# Schematic.net
KiCad netlist of a schematic drawn in EAGLE
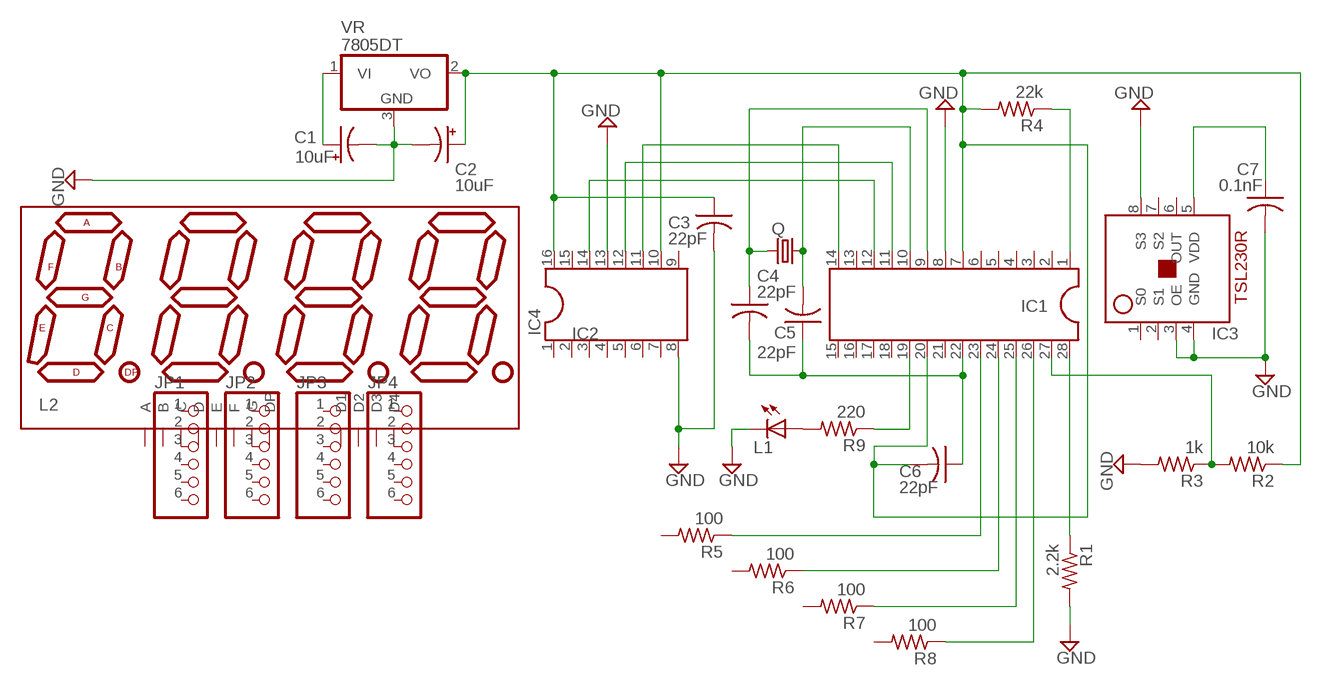
[diagram p0: schematic, sheet 1]

(export (version "E")
  (design (tool "Eeschema 10.0.6"))
  (components
    (comp (ref "C1")
      (value "10uF")
      (footprint "eagle-import:140CLH-1010")
      (libsource (lib "eagle-import") (part "CPOL-US140CLH-1010"))
    )
    (comp (ref "C2")
      (value "10uF")
      (footprint "eagle-import:140CLH-1010")
      (libsource (lib "eagle-import") (part "CPOL-US140CLH-1010"))
    )
    (comp (ref "C3")
      (value "22pF")
      (footprint "eagle-import:C025-024X044")
      (libsource (lib "eagle-import") (part "C-US025-024X044"))
    )
    (comp (ref "C4")
      (value "22pF")
      (footprint "eagle-import:C025-024X044")
      (libsource (lib "eagle-import") (part "C-US025-024X044"))
    )
    (comp (ref "C5")
      (value "22pF")
      (footprint "eagle-import:C025-024X044")
      (libsource (lib "eagle-import") (part "C-US025-024X044"))
    )
    (comp (ref "C6")
      (value "22pF")
      (footprint "eagle-import:C025-024X044")
      (libsource (lib "eagle-import") (part "C-US025-024X044"))
    )
    (comp (ref "C7")
      (value "0.1nF")
      (footprint "eagle-import:C025-024X044")
      (libsource (lib "eagle-import") (part "C-US025-024X044"))
    )
    (comp (ref "IC1")
      (value "DIL28")
      (footprint "eagle-import:DIL28-6")
      (libsource (lib "eagle-import") (part "DIL28"))
    )
    (comp (ref "IC3")
      (value "LIGHT_TO_FREQ_CONVERTER")
      (footprint "eagle-import:LIGHT_TO_FREQ_CONVERTER")
      (libsource (lib "eagle-import") (part "LIGHT_TO_FREQ_CONVERTER"))
    )
    (comp (ref "IC4")
      (value "DIL16")
      (footprint "eagle-import:DIL16")
      (libsource (lib "eagle-import") (part "DIL16"))
    )
    (comp (ref "JP1")
      (value "PINHD-1X6CLEAN")
      (footprint "eagle-import:1X06-CLEAN")
      (libsource (lib "eagle-import") (part "PINHD-1X6CLEAN"))
    )
    (comp (ref "JP2")
      (value "PINHD-1X6CLEAN")
      (footprint "eagle-import:1X06-CLEAN")
      (libsource (lib "eagle-import") (part "PINHD-1X6CLEAN"))
    )
    (comp (ref "JP3")
      (value "PINHD-1X6CLEAN")
      (footprint "eagle-import:1X06-CLEAN")
      (libsource (lib "eagle-import") (part "PINHD-1X6CLEAN"))
    )
    (comp (ref "JP4")
      (value "PINHD-1X6CLEAN")
      (footprint "eagle-import:1X06-CLEAN")
      (libsource (lib "eagle-import") (part "PINHD-1X6CLEAN"))
    )
    (comp (ref "L1")
      (value "LEDIRL80A")
      (footprint "eagle-import:IRL80A")
      (libsource (lib "eagle-import") (part "LEDIRL80A"))
    )
    (comp (ref "Q")
      (value "CRYSTALHC49S")
      (footprint "eagle-import:HC49_S")
      (libsource (lib "eagle-import") (part "CRYSTALHC49S"))
    )
    (comp (ref "R1")
      (value "2.2k")
      (footprint "eagle-import:0207_12")
      (libsource (lib "eagle-import") (part "R-US_0207/12"))
    )
    (comp (ref "R2")
      (value "10k")
      (footprint "eagle-import:0207_12")
      (libsource (lib "eagle-import") (part "R-US_0207/12"))
    )
    (comp (ref "R3")
      (value "1k")
      (footprint "eagle-import:0207_12")
      (libsource (lib "eagle-import") (part "R-US_0207/12"))
    )
    (comp (ref "R4")
      (value "22k")
      (footprint "eagle-import:0207_12")
      (libsource (lib "eagle-import") (part "R-US_0207/12"))
    )
    (comp (ref "R5")
      (value "100")
      (footprint "eagle-import:0207_12")
      (libsource (lib "eagle-import") (part "R-US_0207/12"))
    )
    (comp (ref "R6")
      (value "100")
      (footprint "eagle-import:0207_12")
      (libsource (lib "eagle-import") (part "R-US_0207/12"))
    )
    (comp (ref "R7")
      (value "100")
      (footprint "eagle-import:0207_12")
      (libsource (lib "eagle-import") (part "R-US_0207/12"))
    )
    (comp (ref "R8")
      (value "100")
      (footprint "eagle-import:0207_12")
      (libsource (lib "eagle-import") (part "R-US_0207/12"))
    )
    (comp (ref "R9")
      (value "220")
      (footprint "eagle-import:0207_12")
      (libsource (lib "eagle-import") (part "R-US_0207/12"))
    )
    (comp (ref "U$1")
      (value "7-SEGMENT-4DIGIT-COUNTERPTH")
      (footprint "eagle-import:7-SEGMENT-4DIGIT-COUNTER")
      (libsource (lib "eagle-import") (part "7-SEGMENT-4DIGIT-COUNTERPTH"))
    )
    (comp (ref "VR")
      (value "7805DT")
      (footprint "eagle-import:TO252")
      (libsource (lib "eagle-import") (part "78DT05"))
    )
  )
  (nets
    (net (code "1") (name "GND") (class "Default")
      (node (ref "C1") (pin "-") (pinfunction "-_-") (pintype "passive"))
      (node (ref "C2") (pin "-") (pinfunction "-_-") (pintype "passive"))
      (node (ref "C3") (pin "2") (pinfunction "2_2") (pintype "passive"))
      (node (ref "C7") (pin "2") (pinfunction "2_2") (pintype "passive"))
      (node (ref "IC1") (pin "8") (pinfunction "8_8") (pintype "passive"))
      (node (ref "IC3") (pin "3") (pinfunction "OE_3") (pintype "bidirectional"))
      (node (ref "IC3") (pin "4") (pinfunction "GND_4") (pintype "bidirectional"))
      (node (ref "IC3") (pin "8") (pinfunction "S3_8") (pintype "bidirectional"))
      (node (ref "IC4") (pin "13") (pinfunction "13_13") (pintype "passive"))
      (node (ref "IC4") (pin "8") (pinfunction "8_8") (pintype "passive"))
      (node (ref "L1") (pin "K") (pinfunction "C_K") (pintype "passive"))
      (node (ref "R1") (pin "2") (pinfunction "2_2") (pintype "passive"))
      (node (ref "R3") (pin "2") (pinfunction "2_2") (pintype "passive"))
      (node (ref "VR") (pin "3") (pinfunction "GND_3") (pintype "passive"))
    )
    (net (code "2") (name "Net-(C4-Pad1)") (class "Default")
      (node (ref "C4") (pin "1") (pinfunction "1_1") (pintype "passive"))
      (node (ref "IC1") (pin "9") (pinfunction "9_9") (pintype "passive"))
      (node (ref "Q") (pin "2") (pinfunction "2_2") (pintype "passive"))
    )
    (net (code "3") (name "Net-(C4-Pad2)") (class "Default")
      (node (ref "C4") (pin "2") (pinfunction "2_2") (pintype "passive"))
      (node (ref "C5") (pin "1") (pinfunction "1_1") (pintype "passive"))
      (node (ref "C6") (pin "1") (pinfunction "1_1") (pintype "passive"))
      (node (ref "IC1") (pin "22") (pinfunction "22_22") (pintype "passive"))
    )
    (net (code "4") (name "Net-(C5-Pad2)") (class "Default")
      (node (ref "C5") (pin "2") (pinfunction "2_2") (pintype "passive"))
      (node (ref "IC1") (pin "10") (pinfunction "10_10") (pintype "passive"))
      (node (ref "Q") (pin "1") (pinfunction "1_1") (pintype "passive"))
    )
    (net (code "5") (name "Net-(IC1-Pad1)") (class "Default")
      (node (ref "IC1") (pin "1") (pinfunction "1_1") (pintype "passive"))
      (node (ref "R4") (pin "1") (pinfunction "1_1") (pintype "passive"))
    )
    (net (code "6") (name "Net-(IC1-Pad11)") (class "Default")
      (node (ref "IC1") (pin "11") (pinfunction "11_11") (pintype "passive"))
      (node (ref "IC4") (pin "12") (pinfunction "12_12") (pintype "passive"))
    )
    (net (code "7") (name "Net-(IC1-Pad12)") (class "Default")
      (node (ref "IC1") (pin "12") (pinfunction "12_12") (pintype "passive"))
      (node (ref "IC4") (pin "14") (pinfunction "14_14") (pintype "passive"))
    )
    (net (code "8") (name "Net-(IC1-Pad14)") (class "Default")
      (node (ref "IC1") (pin "14") (pinfunction "14_14") (pintype "passive"))
      (node (ref "IC4") (pin "11") (pinfunction "11_11") (pintype "passive"))
    )
    (net (code "9") (name "Net-(IC1-Pad19)") (class "Default")
      (node (ref "IC1") (pin "19") (pinfunction "19_19") (pintype "passive"))
      (node (ref "R9") (pin "1") (pinfunction "1_1") (pintype "passive"))
    )
    (net (code "10") (name "Net-(IC1-Pad23)") (class "Default")
      (node (ref "IC1") (pin "23") (pinfunction "23_23") (pintype "passive"))
      (node (ref "R5") (pin "1") (pinfunction "1_1") (pintype "passive"))
    )
    (net (code "11") (name "Net-(IC1-Pad24)") (class "Default")
      (node (ref "IC1") (pin "24") (pinfunction "24_24") (pintype "passive"))
      (node (ref "R6") (pin "1") (pinfunction "1_1") (pintype "passive"))
    )
    (net (code "12") (name "Net-(IC1-Pad25)") (class "Default")
      (node (ref "IC1") (pin "25") (pinfunction "25_25") (pintype "passive"))
      (node (ref "R7") (pin "1") (pinfunction "1_1") (pintype "passive"))
    )
    (net (code "13") (name "Net-(IC1-Pad26)") (class "Default")
      (node (ref "IC1") (pin "26") (pinfunction "26_26") (pintype "passive"))
      (node (ref "R8") (pin "1") (pinfunction "1_1") (pintype "passive"))
    )
    (net (code "14") (name "Net-(IC1-Pad27)") (class "Default")
      (node (ref "IC1") (pin "27") (pinfunction "27_27") (pintype "passive"))
      (node (ref "R2") (pin "2") (pinfunction "2_2") (pintype "passive"))
      (node (ref "R3") (pin "1") (pinfunction "1_1") (pintype "passive"))
    )
    (net (code "15") (name "Net-(IC1-Pad28)") (class "Default")
      (node (ref "IC1") (pin "28") (pinfunction "28_28") (pintype "passive"))
      (node (ref "R1") (pin "1") (pinfunction "1_1") (pintype "passive"))
    )
    (net (code "16") (name "Net-(IC3-VDD)") (class "Default")
      (node (ref "C7") (pin "1") (pinfunction "1_1") (pintype "passive"))
      (node (ref "IC3") (pin "5") (pinfunction "VDD_5") (pintype "bidirectional"))
    )
    (net (code "17") (name "Net-(L1-PadA)") (class "Default")
      (node (ref "L1") (pin "A") (pinfunction "A_A") (pintype "passive"))
      (node (ref "R9") (pin "2") (pinfunction "2_2") (pintype "passive"))
    )
    (net (code "18") (name "Net-(U$1-C)") (class "Default")
      (node (ref "JP1") (pin "3") (pinfunction "3_3") (pintype "passive"))
      (node (ref "U$1") (pin "4") (pinfunction "C_4") (pintype "bidirectional"))
    )
    (net (code "19") (name "Net-(U$1-D4)") (class "Default")
      (node (ref "JP4") (pin "3") (pinfunction "3_3") (pintype "passive"))
      (node (ref "U$1") (pin "6") (pinfunction "D4_6") (pintype "bidirectional"))
    )
    (net (code "20") (name "Net-(U$1-G)") (class "Default")
      (node (ref "JP2") (pin "3") (pinfunction "3_3") (pintype "passive"))
      (node (ref "U$1") (pin "5") (pinfunction "G_5") (pintype "bidirectional"))
    )
    (net (code "21") (name "Net-(VR-VI)") (class "Default")
      (node (ref "C1") (pin "+") (pinfunction "+_+") (pintype "passive"))
      (node (ref "VR") (pin "1") (pinfunction "VI_1") (pintype "input"))
    )
    (net (code "22") (name "Net-(VR-VO)") (class "Default")
      (node (ref "C2") (pin "+") (pinfunction "+_+") (pintype "passive"))
      (node (ref "C3") (pin "1") (pinfunction "1_1") (pintype "passive"))
      (node (ref "C6") (pin "2") (pinfunction "2_2") (pintype "passive"))
      (node (ref "IC1") (pin "20") (pinfunction "20_20") (pintype "passive"))
      (node (ref "IC1") (pin "7") (pinfunction "7_7") (pintype "passive"))
      (node (ref "IC4") (pin "10") (pinfunction "10_10") (pintype "passive"))
      (node (ref "IC4") (pin "16") (pinfunction "16_16") (pintype "passive"))
      (node (ref "R2") (pin "1") (pinfunction "1_1") (pintype "passive"))
      (node (ref "R4") (pin "2") (pinfunction "2_2") (pintype "passive"))
      (node (ref "VR") (pin "2") (pinfunction "VO_2") (pintype "passive"))
    )
    (net (code "23") (name "unconnected-(IC1-Pad2)") (class "Default")
      (node (ref "IC1") (pin "2") (pinfunction "2_2") (pintype "passive"))
    )
    (net (code "24") (name "unconnected-(IC1-Pad3)") (class "Default")
      (node (ref "IC1") (pin "3") (pinfunction "3_3") (pintype "passive"))
    )
    (net (code "25") (name "unconnected-(IC1-Pad4)") (class "Default")
      (node (ref "IC1") (pin "4") (pinfunction "4_4") (pintype "passive"))
    )
    (net (code "26") (name "unconnected-(IC1-Pad5)") (class "Default")
      (node (ref "IC1") (pin "5") (pinfunction "5_5") (pintype "passive"))
    )
    (net (code "27") (name "unconnected-(IC1-Pad6)") (class "Default")
      (node (ref "IC1") (pin "6") (pinfunction "6_6") (pintype "passive"))
    )
    (net (code "28") (name "unconnected-(IC1-Pad13)") (class "Default")
      (node (ref "IC1") (pin "13") (pinfunction "13_13") (pintype "passive"))
    )
    (net (code "29") (name "unconnected-(IC1-Pad15)") (class "Default")
      (node (ref "IC1") (pin "15") (pinfunction "15_15") (pintype "passive"))
    )
    (net (code "30") (name "unconnected-(IC1-Pad16)") (class "Default")
      (node (ref "IC1") (pin "16") (pinfunction "16_16") (pintype "passive"))
    )
    (net (code "31") (name "unconnected-(IC1-Pad17)") (class "Default")
      (node (ref "IC1") (pin "17") (pinfunction "17_17") (pintype "passive"))
    )
    (net (code "32") (name "unconnected-(IC1-Pad18)") (class "Default")
      (node (ref "IC1") (pin "18") (pinfunction "18_18") (pintype "passive"))
    )
    (net (code "33") (name "unconnected-(IC1-Pad21)") (class "Default")
      (node (ref "IC1") (pin "21") (pinfunction "21_21") (pintype "passive"))
    )
    (net (code "34") (name "unconnected-(IC3-OUT-Pad6)") (class "Default")
      (node (ref "IC3") (pin "6") (pinfunction "OUT_6") (pintype "bidirectional"))
    )
    (net (code "35") (name "unconnected-(IC3-S0-Pad1)") (class "Default")
      (node (ref "IC3") (pin "1") (pinfunction "S0_1") (pintype "bidirectional"))
    )
    (net (code "36") (name "unconnected-(IC3-S1-Pad2)") (class "Default")
      (node (ref "IC3") (pin "2") (pinfunction "S1_2") (pintype "bidirectional"))
    )
    (net (code "37") (name "unconnected-(IC3-S2-Pad7)") (class "Default")
      (node (ref "IC3") (pin "7") (pinfunction "S2_7") (pintype "bidirectional"))
    )
    (net (code "38") (name "unconnected-(IC4-Pad1)") (class "Default")
      (node (ref "IC4") (pin "1") (pinfunction "1_1") (pintype "passive"))
    )
    (net (code "39") (name "unconnected-(IC4-Pad2)") (class "Default")
      (node (ref "IC4") (pin "2") (pinfunction "2_2") (pintype "passive"))
    )
    (net (code "40") (name "unconnected-(IC4-Pad3)") (class "Default")
      (node (ref "IC4") (pin "3") (pinfunction "3_3") (pintype "passive"))
    )
    (net (code "41") (name "unconnected-(IC4-Pad4)") (class "Default")
      (node (ref "IC4") (pin "4") (pinfunction "4_4") (pintype "passive"))
    )
    (net (code "42") (name "unconnected-(IC4-Pad5)") (class "Default")
      (node (ref "IC4") (pin "5") (pinfunction "5_5") (pintype "passive"))
    )
    (net (code "43") (name "unconnected-(IC4-Pad6)") (class "Default")
      (node (ref "IC4") (pin "6") (pinfunction "6_6") (pintype "passive"))
    )
    (net (code "44") (name "unconnected-(IC4-Pad7)") (class "Default")
      (node (ref "IC4") (pin "7") (pinfunction "7_7") (pintype "passive"))
    )
    (net (code "45") (name "unconnected-(IC4-Pad9)") (class "Default")
      (node (ref "IC4") (pin "9") (pinfunction "9_9") (pintype "passive"))
    )
    (net (code "46") (name "unconnected-(IC4-Pad15)") (class "Default")
      (node (ref "IC4") (pin "15") (pinfunction "15_15") (pintype "passive"))
    )
    (net (code "47") (name "unconnected-(JP1-Pad1)") (class "Default")
      (node (ref "JP1") (pin "1") (pinfunction "1_1") (pintype "passive"))
    )
    (net (code "48") (name "unconnected-(JP1-Pad2)") (class "Default")
      (node (ref "JP1") (pin "2") (pinfunction "2_2") (pintype "passive"))
    )
    (net (code "49") (name "unconnected-(JP1-Pad4)") (class "Default")
      (node (ref "JP1") (pin "4") (pinfunction "4_4") (pintype "passive"))
    )
    (net (code "50") (name "unconnected-(JP1-Pad5)") (class "Default")
      (node (ref "JP1") (pin "5") (pinfunction "5_5") (pintype "passive"))
    )
    (net (code "51") (name "unconnected-(JP1-Pad6)") (class "Default")
      (node (ref "JP1") (pin "6") (pinfunction "6_6") (pintype "passive"))
    )
    (net (code "52") (name "unconnected-(JP2-Pad1)") (class "Default")
      (node (ref "JP2") (pin "1") (pinfunction "1_1") (pintype "passive"))
    )
    (net (code "53") (name "unconnected-(JP2-Pad2)") (class "Default")
      (node (ref "JP2") (pin "2") (pinfunction "2_2") (pintype "passive"))
    )
    (net (code "54") (name "unconnected-(JP2-Pad4)") (class "Default")
      (node (ref "JP2") (pin "4") (pinfunction "4_4") (pintype "passive"))
    )
    (net (code "55") (name "unconnected-(JP2-Pad5)") (class "Default")
      (node (ref "JP2") (pin "5") (pinfunction "5_5") (pintype "passive"))
    )
    (net (code "56") (name "unconnected-(JP2-Pad6)") (class "Default")
      (node (ref "JP2") (pin "6") (pinfunction "6_6") (pintype "passive"))
    )
    (net (code "57") (name "unconnected-(JP3-Pad1)") (class "Default")
      (node (ref "JP3") (pin "1") (pinfunction "1_1") (pintype "passive"))
    )
    (net (code "58") (name "unconnected-(JP3-Pad2)") (class "Default")
      (node (ref "JP3") (pin "2") (pinfunction "2_2") (pintype "passive"))
    )
    (net (code "59") (name "unconnected-(JP3-Pad3)") (class "Default")
      (node (ref "JP3") (pin "3") (pinfunction "3_3") (pintype "passive"))
    )
    (net (code "60") (name "unconnected-(JP3-Pad4)") (class "Default")
      (node (ref "JP3") (pin "4") (pinfunction "4_4") (pintype "passive"))
    )
    (net (code "61") (name "unconnected-(JP3-Pad5)") (class "Default")
      (node (ref "JP3") (pin "5") (pinfunction "5_5") (pintype "passive"))
    )
    (net (code "62") (name "unconnected-(JP3-Pad6)") (class "Default")
      (node (ref "JP3") (pin "6") (pinfunction "6_6") (pintype "passive"))
    )
    (net (code "63") (name "unconnected-(JP4-Pad1)") (class "Default")
      (node (ref "JP4") (pin "1") (pinfunction "1_1") (pintype "passive"))
    )
    (net (code "64") (name "unconnected-(JP4-Pad2)") (class "Default")
      (node (ref "JP4") (pin "2") (pinfunction "2_2") (pintype "passive"))
    )
    (net (code "65") (name "unconnected-(JP4-Pad4)") (class "Default")
      (node (ref "JP4") (pin "4") (pinfunction "4_4") (pintype "passive"))
    )
    (net (code "66") (name "unconnected-(JP4-Pad5)") (class "Default")
      (node (ref "JP4") (pin "5") (pinfunction "5_5") (pintype "passive"))
    )
    (net (code "67") (name "unconnected-(JP4-Pad6)") (class "Default")
      (node (ref "JP4") (pin "6") (pinfunction "6_6") (pintype "passive"))
    )
    (net (code "68") (name "unconnected-(R5-Pad2)") (class "Default")
      (node (ref "R5") (pin "2") (pinfunction "2_2") (pintype "passive"))
    )
    (net (code "69") (name "unconnected-(R6-Pad2)") (class "Default")
      (node (ref "R6") (pin "2") (pinfunction "2_2") (pintype "passive"))
    )
    (net (code "70") (name "unconnected-(R7-Pad2)") (class "Default")
      (node (ref "R7") (pin "2") (pinfunction "2_2") (pintype "passive"))
    )
    (net (code "71") (name "unconnected-(R8-Pad2)") (class "Default")
      (node (ref "R8") (pin "2") (pinfunction "2_2") (pintype "passive"))
    )
    (net (code "72") (name "unconnected-(U$1-A-Pad11)") (class "Default")
      (node (ref "U$1") (pin "11") (pinfunction "A_11") (pintype "bidirectional"))
    )
    (net (code "73") (name "unconnected-(U$1-B-Pad7)") (class "Default")
      (node (ref "U$1") (pin "7") (pinfunction "B_7") (pintype "bidirectional"))
    )
    (net (code "74") (name "unconnected-(U$1-D-Pad2)") (class "Default")
      (node (ref "U$1") (pin "2") (pinfunction "D_2") (pintype "bidirectional"))
    )
    (net (code "75") (name "unconnected-(U$1-D1-Pad12)") (class "Default")
      (node (ref "U$1") (pin "12") (pinfunction "D1_12") (pintype "bidirectional"))
    )
    (net (code "76") (name "unconnected-(U$1-D2-Pad9)") (class "Default")
      (node (ref "U$1") (pin "9") (pinfunction "D2_9") (pintype "bidirectional"))
    )
    (net (code "77") (name "unconnected-(U$1-D3-Pad8)") (class "Default")
      (node (ref "U$1") (pin "8") (pinfunction "D3_8") (pintype "bidirectional"))
    )
    (net (code "78") (name "unconnected-(U$1-DP-Pad3)") (class "Default")
      (node (ref "U$1") (pin "3") (pinfunction "DP_3") (pintype "bidirectional"))
    )
    (net (code "79") (name "unconnected-(U$1-E-Pad1)") (class "Default")
      (node (ref "U$1") (pin "1") (pinfunction "E_1") (pintype "bidirectional"))
    )
    (net (code "80") (name "unconnected-(U$1-F-Pad10)") (class "Default")
      (node (ref "U$1") (pin "10") (pinfunction "F_10") (pintype "bidirectional"))
    )
  )
)
